# SCH_PCB-Card_2024-06-21.net
KiCad netlist of a schematic drawn in EasyEDA
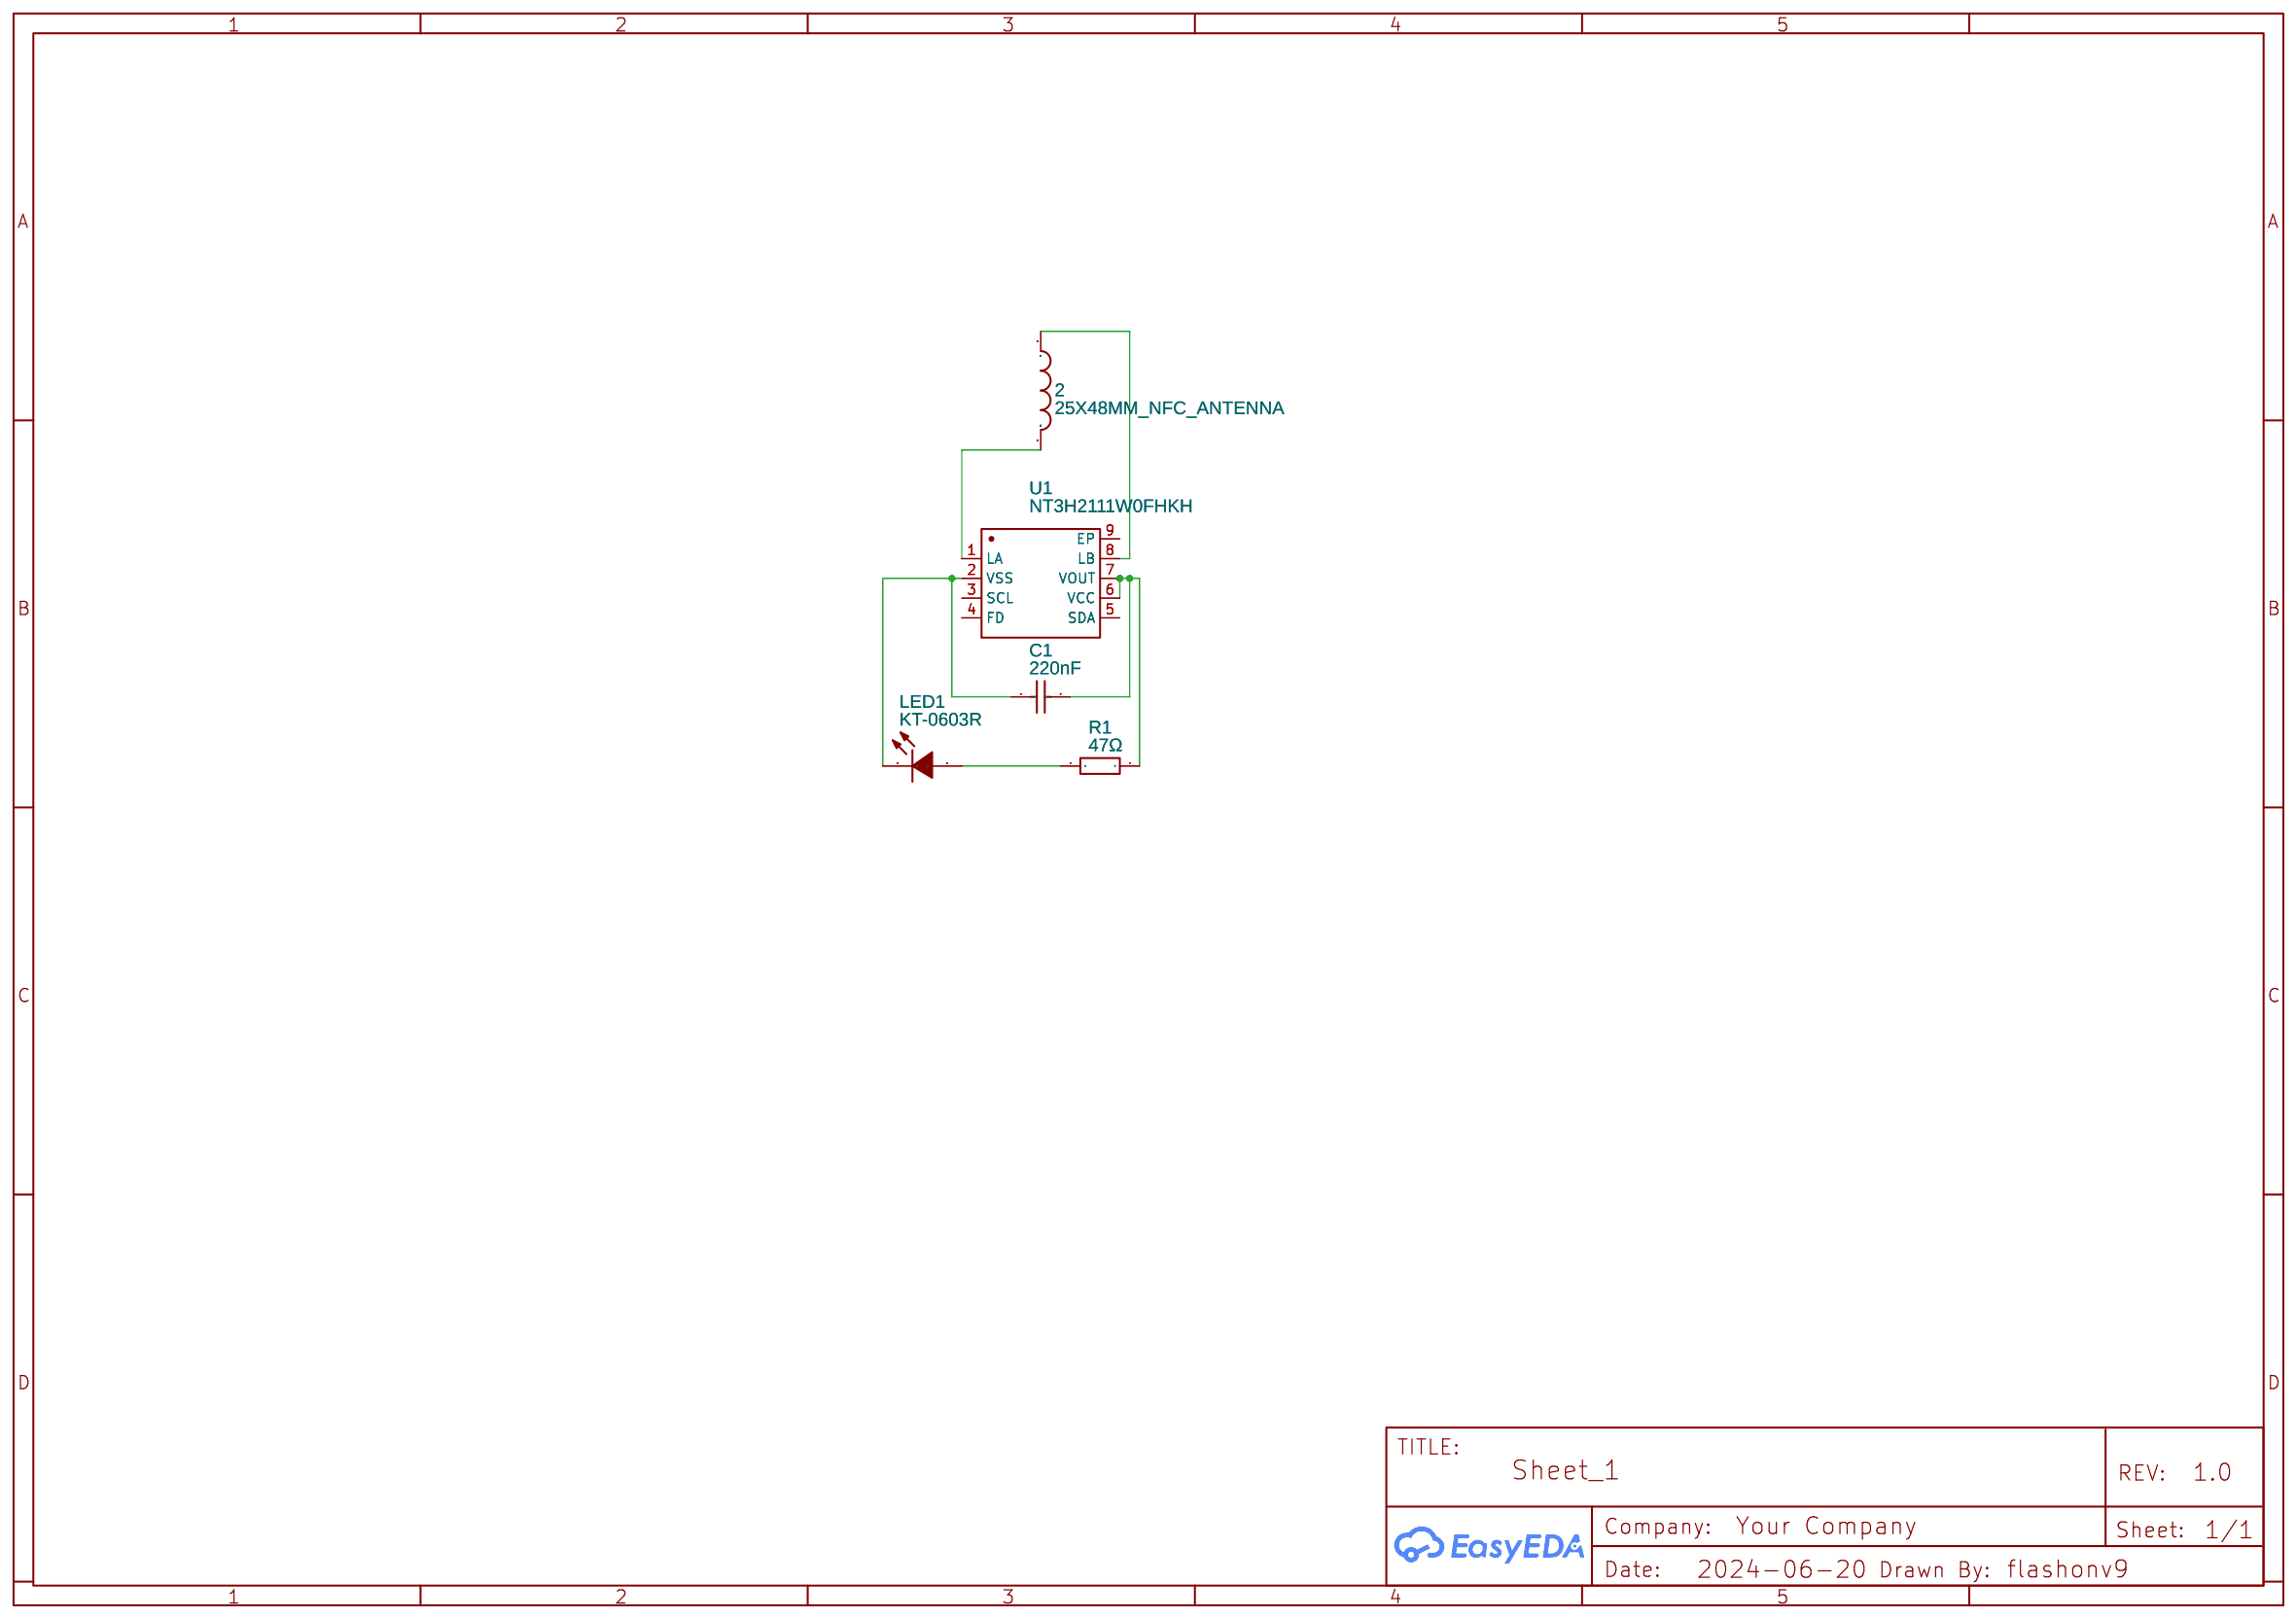
[diagram p0: schematic sheet]

(export (version "E")
  (design (tool "Eeschema 10.0.6"))
  (components
    (comp (ref "2") (value "25X48MM_NFC_ANTENNA") (libsource (lib "") (part "25X48MM_NFC_ANTENNA")))
    (comp (ref "C1")
      (value "220nF")
      (fields
        (field (name "Manufacturer Part") "CL10B224KA8NNNC")
        (field (name "Manufacturer") "SAMSUNG(三星)")
      )
      (libsource (lib "") (part "CL10B224KA8NNNC"))
    )
    (comp (ref "LED1")
      (value "KT-0603R")
      (fields (field (name "Manufacturer") "KENTO"))
      (libsource (lib "") (part "KT-0603R"))
    )
    (comp (ref "R1")
      (value "47Ω")
      (fields
        (field (name "Manufacturer Part") "0603WAF470JT5E")
        (field (name "Manufacturer") "UNI-ROYAL(厚声)")
      )
      (libsource (lib "") (part "0603WAF470JT5E"))
    )
    (comp (ref "U1")
      (value "NT3H2111W0FHKH")
      (fields (field (name "Manufacturer") "NXP(恩智浦)"))
      (libsource (lib "") (part "NT3H2111W0FHKH"))
    )
  )
  (nets
    (net (code "1") (name "Net-(LED1-A)") (class "Default")
      (node (ref "LED1") (pin "2") (pinfunction "A_2") (pintype "unspecified"))
      (node (ref "R1") (pin "1") (pinfunction "1_1") (pintype "input"))
    )
    (net (code "2") (name "Net-(LED1-K)") (class "Default")
      (node (ref "C1") (pin "1") (pinfunction "1_1") (pintype "input"))
      (node (ref "LED1") (pin "1") (pinfunction "K_1") (pintype "unspecified"))
      (node (ref "U1") (pin "2") (pinfunction "VSS_2") (pintype "unspecified"))
    )
    (net (code "3") (name "Net-(U1-LA)") (class "Default")
      (node (ref "2") (pin "P$2") (pinfunction "P$2_P$2") (pintype "bidirectional"))
      (node (ref "U1") (pin "1") (pinfunction "LA_1") (pintype "unspecified"))
    )
    (net (code "4") (name "Net-(U1-LB)") (class "Default")
      (node (ref "2") (pin "P$1") (pinfunction "P$1_P$1") (pintype "bidirectional"))
      (node (ref "U1") (pin "8") (pinfunction "LB_8") (pintype "unspecified"))
    )
    (net (code "5") (name "Net-(U1-VCC)") (class "Default")
      (node (ref "C1") (pin "2") (pinfunction "2_2") (pintype "input"))
      (node (ref "R1") (pin "2") (pinfunction "2_2") (pintype "input"))
      (node (ref "U1") (pin "6") (pinfunction "VCC_6") (pintype "unspecified"))
      (node (ref "U1") (pin "7") (pinfunction "VOUT_7") (pintype "unspecified"))
    )
    (net (code "6") (name "unconnected-(U1-EP-Pad9)") (class "Default")
      (node (ref "U1") (pin "9") (pinfunction "EP_9") (pintype "unspecified"))
    )
    (net (code "7") (name "unconnected-(U1-FD-Pad4)") (class "Default")
      (node (ref "U1") (pin "4") (pinfunction "FD_4") (pintype "unspecified"))
    )
    (net (code "8") (name "unconnected-(U1-SCL-Pad3)") (class "Default")
      (node (ref "U1") (pin "3") (pinfunction "SCL_3") (pintype "unspecified"))
    )
    (net (code "9") (name "unconnected-(U1-SDA-Pad5)") (class "Default")
      (node (ref "U1") (pin "5") (pinfunction "SDA_5") (pintype "unspecified"))
    )
  )
)
